# resistors_set.net
KiCad netlist of a schematic drawn in Altium Designer
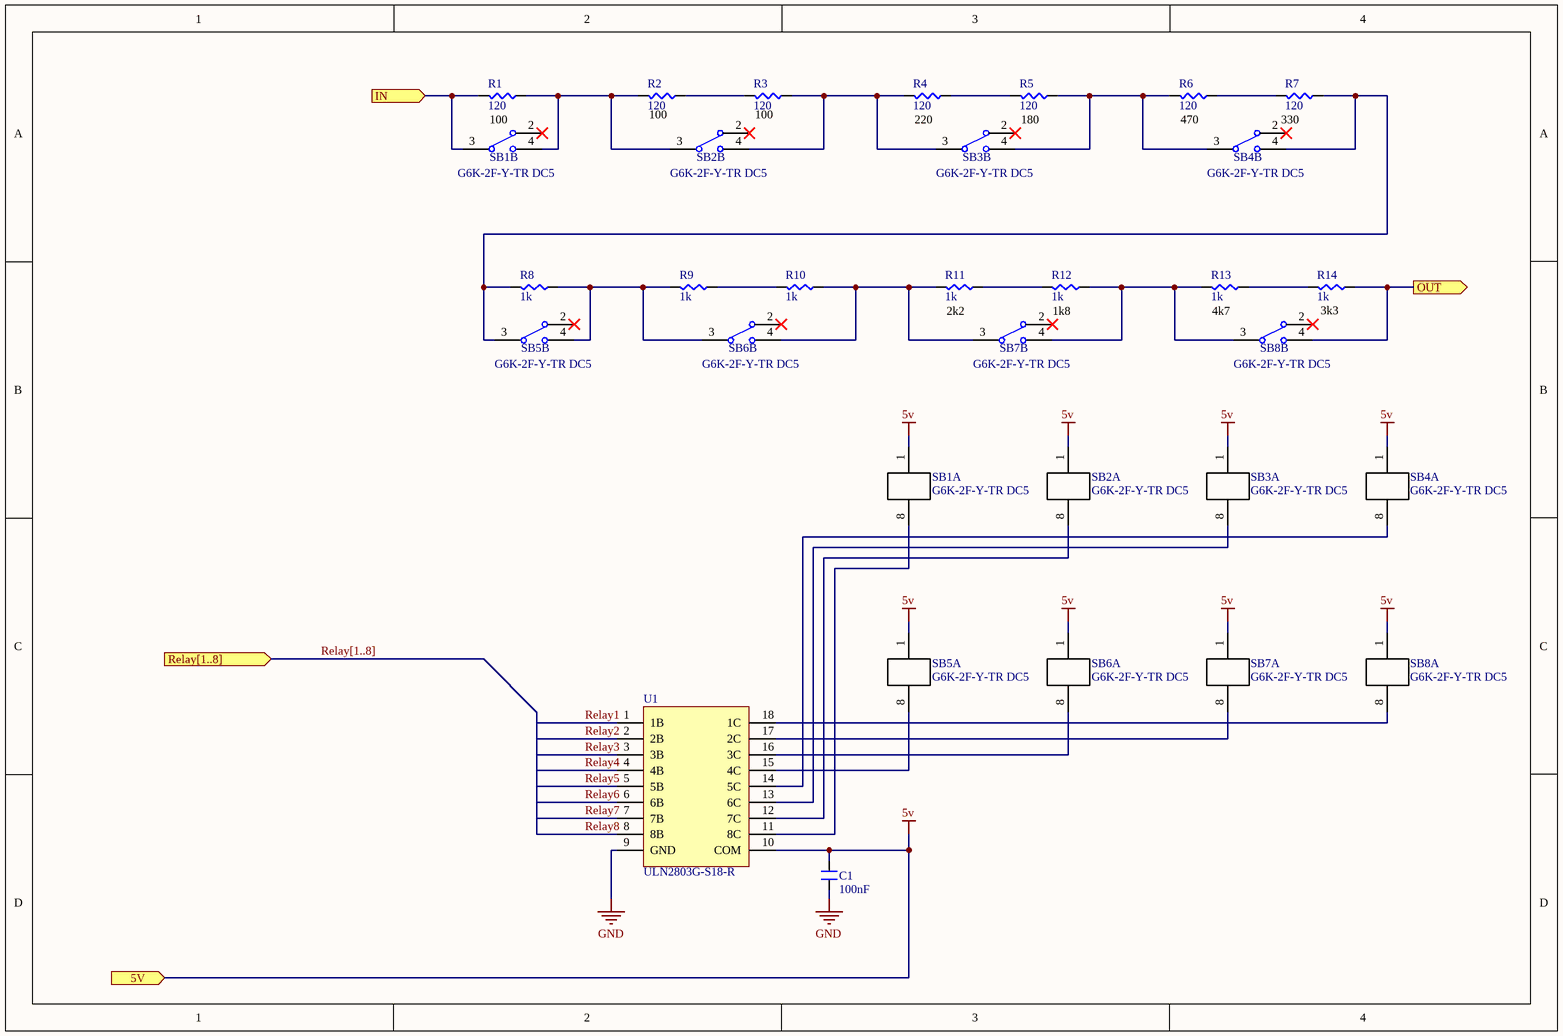
[diagram p0: resistors_set.SchDoc]

(export (version "E")
  (design (tool "Eeschema 10.0.6"))
  (components
    (comp (ref "C1")
      (value "100nF")
      (footprint "CAP0603")
      (description "Tolerance ±10%\nRated Voltage 50Vdc\nTemperature 0±30ppm/℃")
      (fields (field (name "PART NUMBER") "GCM188R71H104KA57J") (field (name "TOLERANCE") "10%"))
      (libsource (lib "Lib_Kam") (part "Capacitor"))
    )
    (comp (ref "R1")
      (value "120")
      (footprint "RES1206")
      (description "Tolerance ±1%\nPower (Watts) 0.25W, 1/4W\nTemperature Coefficient ±100ppm/°C")
      (fields (field (name "PART NUMBER") "CR1206-FX-1200ELF") (field (name "TOLERANCE") "1%"))
      (libsource (lib "Lib_Kam") (part "Resistor"))
    )
    (comp (ref "R2")
      (value "120")
      (footprint "RES1206")
      (description "Tolerance ±1%\nPower (Watts) 0.25W, 1/4W\nTemperature Coefficient ±100ppm/°C")
      (fields (field (name "PART NUMBER") "CR1206-FX-1200ELF") (field (name "TOLERANCE") "1%"))
      (libsource (lib "Lib_Kam") (part "Resistor"))
    )
    (comp (ref "R3")
      (value "120")
      (footprint "RES1206")
      (description "Tolerance ±1%\nPower (Watts) 0.25W, 1/4W\nTemperature Coefficient ±100ppm/°C")
      (fields (field (name "PART NUMBER") "CR1206-FX-1200ELF") (field (name "TOLERANCE") "1%"))
      (libsource (lib "Lib_Kam") (part "Resistor"))
    )
    (comp (ref "R4")
      (value "120")
      (footprint "RES1206")
      (description "Tolerance ±1%\nPower (Watts) 0.25W, 1/4W\nTemperature Coefficient ±100ppm/°C")
      (fields (field (name "PART NUMBER") "CR1206-FX-1200ELF") (field (name "TOLERANCE") "1%"))
      (libsource (lib "Lib_Kam") (part "Resistor"))
    )
    (comp (ref "R5")
      (value "120")
      (footprint "RES1206")
      (description "Tolerance ±1%\nPower (Watts) 0.25W, 1/4W\nTemperature Coefficient ±100ppm/°C")
      (fields (field (name "PART NUMBER") "CR1206-FX-1200ELF") (field (name "TOLERANCE") "1%"))
      (libsource (lib "Lib_Kam") (part "Resistor"))
    )
    (comp (ref "R6")
      (value "120")
      (footprint "RES1206")
      (description "Tolerance ±1%\nPower (Watts) 0.25W, 1/4W\nTemperature Coefficient ±100ppm/°C")
      (fields (field (name "PART NUMBER") "CR1206-FX-1200ELF") (field (name "TOLERANCE") "1%"))
      (libsource (lib "Lib_Kam") (part "Resistor"))
    )
    (comp (ref "R7")
      (value "120")
      (footprint "RES1206")
      (description "Tolerance ±1%\nPower (Watts) 0.25W, 1/4W\nTemperature Coefficient ±100ppm/°C")
      (fields (field (name "PART NUMBER") "CR1206-FX-1200ELF") (field (name "TOLERANCE") "1%"))
      (libsource (lib "Lib_Kam") (part "Resistor"))
    )
    (comp (ref "R8")
      (value "1k")
      (footprint "RES1206")
      (description "Tolerance ±1%\nPower (Watts) 0.1W, 1/10W\nTemperature Coefficient ±50ppm/°C")
      (fields (field (name "PART NUMBER") "CRT1206-FZ-1001ELF") (field (name "TOLERANCE") "1%"))
      (libsource (lib "Lib_Kam") (part "Resistor"))
    )
    (comp (ref "R9")
      (value "1k")
      (footprint "RES1206")
      (description "Tolerance ±1%\nPower (Watts) 0.1W, 1/10W\nTemperature Coefficient ±50ppm/°C")
      (fields (field (name "PART NUMBER") "CRT1206-FZ-1001ELF") (field (name "TOLERANCE") "1%"))
      (libsource (lib "Lib_Kam") (part "Resistor"))
    )
    (comp (ref "R10")
      (value "1k")
      (footprint "RES1206")
      (description "Tolerance ±1%\nPower (Watts) 0.1W, 1/10W\nTemperature Coefficient ±50ppm/°C")
      (fields (field (name "PART NUMBER") "CRT1206-FZ-1001ELF") (field (name "TOLERANCE") "1%"))
      (libsource (lib "Lib_Kam") (part "Resistor"))
    )
    (comp (ref "R11")
      (value "1k")
      (footprint "RES1206")
      (description "Tolerance ±1%\nPower (Watts) 0.1W, 1/10W\nTemperature Coefficient ±50ppm/°C")
      (fields (field (name "PART NUMBER") "CRT1206-FZ-1001ELF") (field (name "TOLERANCE") "1%"))
      (libsource (lib "Lib_Kam") (part "Resistor"))
    )
    (comp (ref "R12")
      (value "1k")
      (footprint "RES1206")
      (description "Tolerance ±1%\nPower (Watts) 0.1W, 1/10W\nTemperature Coefficient ±50ppm/°C")
      (fields (field (name "PART NUMBER") "CRT1206-FZ-1001ELF") (field (name "TOLERANCE") "1%"))
      (libsource (lib "Lib_Kam") (part "Resistor"))
    )
    (comp (ref "R13")
      (value "1k")
      (footprint "RES1206")
      (description "Tolerance ±1%\nPower (Watts) 0.1W, 1/10W\nTemperature Coefficient ±50ppm/°C")
      (fields (field (name "PART NUMBER") "CRT1206-FZ-1001ELF") (field (name "TOLERANCE") "1%"))
      (libsource (lib "Lib_Kam") (part "Resistor"))
    )
    (comp (ref "R14")
      (value "1k")
      (footprint "RES1206")
      (description "Tolerance ±1%\nPower (Watts) 0.1W, 1/10W\nTemperature Coefficient ±50ppm/°C")
      (fields (field (name "PART NUMBER") "CRT1206-FZ-1001ELF") (field (name "TOLERANCE") "1%"))
      (libsource (lib "Lib_Kam") (part "Resistor"))
    )
    (comp (ref "SB1")
      (value "G6K-2F-Y-TR DC5")
      (footprint "Omron_G6K-2F-Y")
      (description "1A 5V DPDT (2 Form C) SMD,6.5x10mm Signal Relays ROHS")
      (fields (field (name "MANUFACTURER") "Omron Electronics"))
      (libsource (lib "Lib_Kam") (part "Omron_G6K"))
    )
    (comp (ref "SB2")
      (value "G6K-2F-Y-TR DC5")
      (footprint "Omron_G6K-2F-Y")
      (description "1A 5V DPDT (2 Form C) SMD,6.5x10mm Signal Relays ROHS")
      (fields (field (name "MANUFACTURER") "Omron Electronics"))
      (libsource (lib "Lib_Kam") (part "Omron_G6K"))
    )
    (comp (ref "SB3")
      (value "G6K-2F-Y-TR DC5")
      (footprint "Omron_G6K-2F-Y")
      (description "1A 5V DPDT (2 Form C) SMD,6.5x10mm Signal Relays ROHS")
      (fields (field (name "MANUFACTURER") "Omron Electronics"))
      (libsource (lib "Lib_Kam") (part "Omron_G6K"))
    )
    (comp (ref "SB4")
      (value "G6K-2F-Y-TR DC5")
      (footprint "Omron_G6K-2F-Y")
      (description "1A 5V DPDT (2 Form C) SMD,6.5x10mm Signal Relays ROHS")
      (fields (field (name "MANUFACTURER") "Omron Electronics"))
      (libsource (lib "Lib_Kam") (part "Omron_G6K"))
    )
    (comp (ref "SB5")
      (value "G6K-2F-Y-TR DC5")
      (footprint "Omron_G6K-2F-Y")
      (description "1A 5V DPDT (2 Form C) SMD,6.5x10mm Signal Relays ROHS")
      (fields (field (name "MANUFACTURER") "Omron Electronics"))
      (libsource (lib "Lib_Kam") (part "Omron_G6K"))
    )
    (comp (ref "SB6")
      (value "G6K-2F-Y-TR DC5")
      (footprint "Omron_G6K-2F-Y")
      (description "1A 5V DPDT (2 Form C) SMD,6.5x10mm Signal Relays ROHS")
      (fields (field (name "MANUFACTURER") "Omron Electronics"))
      (libsource (lib "Lib_Kam") (part "Omron_G6K"))
    )
    (comp (ref "SB7")
      (value "G6K-2F-Y-TR DC5")
      (footprint "Omron_G6K-2F-Y")
      (description "1A 5V DPDT (2 Form C) SMD,6.5x10mm Signal Relays ROHS")
      (fields (field (name "MANUFACTURER") "Omron Electronics"))
      (libsource (lib "Lib_Kam") (part "Omron_G6K"))
    )
    (comp (ref "SB8")
      (value "G6K-2F-Y-TR DC5")
      (footprint "Omron_G6K-2F-Y")
      (description "1A 5V DPDT (2 Form C) SMD,6.5x10mm Signal Relays ROHS")
      (fields (field (name "MANUFACTURER") "Omron Electronics"))
      (libsource (lib "Lib_Kam") (part "Omron_G6K"))
    )
    (comp (ref "U1")
      (value "ULN2803G-S18-R")
      (footprint "SOIC-18-wide")
      (description "SOP-18 Darlington Transistor Arrays ROHS")
      (fields (field (name "MANUFACTURER") "UTC(Unisonic Tech)"))
      (libsource (lib "Lib_Kam") (part "ULN2803"))
    )
  )
  (nets
    (net (code "1") (name "/IN") (class "Default")
      (node (ref "R1") (pin "1") (pintype "passive"))
      (node (ref "SB1") (pin "3") (pintype "passive"))
    )
    (net (code "2") (name "/OUT") (class "Default")
      (node (ref "R14") (pin "2") (pintype "passive"))
      (node (ref "SB8") (pin "4") (pintype "passive"))
    )
    (net (code "3") (name "/Relay1") (class "Default")
      (node (ref "U1") (pin "1") (pinfunction "1B_1") (pintype "passive"))
    )
    (net (code "4") (name "/Relay2") (class "Default")
      (node (ref "U1") (pin "2") (pinfunction "2B_2") (pintype "passive"))
    )
    (net (code "5") (name "/Relay3") (class "Default")
      (node (ref "U1") (pin "3") (pinfunction "3B_3") (pintype "passive"))
    )
    (net (code "6") (name "/Relay4") (class "Default")
      (node (ref "U1") (pin "4") (pinfunction "4B_4") (pintype "passive"))
    )
    (net (code "7") (name "/Relay5") (class "Default")
      (node (ref "U1") (pin "5") (pinfunction "5B_5") (pintype "passive"))
    )
    (net (code "8") (name "/Relay6") (class "Default")
      (node (ref "U1") (pin "6") (pinfunction "6B_6") (pintype "passive"))
    )
    (net (code "9") (name "/Relay7") (class "Default")
      (node (ref "U1") (pin "7") (pinfunction "7B_7") (pintype "passive"))
    )
    (net (code "10") (name "/Relay8") (class "Default")
      (node (ref "U1") (pin "8") (pinfunction "8B_8") (pintype "passive"))
    )
    (net (code "12") (name "5v") (class "Default")
      (node (ref "C1") (pin "2") (pinfunction "2_2") (pintype "passive"))
      (node (ref "SB1") (pin "1") (pintype "passive"))
      (node (ref "SB2") (pin "1") (pintype "passive"))
      (node (ref "SB3") (pin "1") (pintype "passive"))
      (node (ref "SB4") (pin "1") (pintype "passive"))
      (node (ref "SB5") (pin "1") (pintype "passive"))
      (node (ref "SB6") (pin "1") (pintype "passive"))
      (node (ref "SB7") (pin "1") (pintype "passive"))
      (node (ref "SB8") (pin "1") (pintype "passive"))
      (node (ref "U1") (pin "10") (pinfunction "COM_10") (pintype "passive"))
    )
    (net (code "13") (name "GND") (class "Default")
      (node (ref "C1") (pin "1") (pinfunction "2_1") (pintype "passive"))
      (node (ref "U1") (pin "9") (pinfunction "GND_9") (pintype "passive"))
    )
    (net (code "14") (name "Net-(R1-Pad2)") (class "Default")
      (node (ref "R1") (pin "2") (pintype "passive"))
      (node (ref "R2") (pin "1") (pintype "passive"))
      (node (ref "SB1") (pin "4") (pintype "passive"))
      (node (ref "SB2") (pin "3") (pintype "passive"))
    )
    (net (code "15") (name "Net-(R2-Pad2)") (class "Default")
      (node (ref "R2") (pin "2") (pintype "passive"))
      (node (ref "R3") (pin "1") (pintype "passive"))
    )
    (net (code "16") (name "Net-(R3-Pad2)") (class "Default")
      (node (ref "R3") (pin "2") (pintype "passive"))
      (node (ref "R4") (pin "1") (pintype "passive"))
      (node (ref "SB2") (pin "4") (pintype "passive"))
      (node (ref "SB3") (pin "3") (pintype "passive"))
    )
    (net (code "17") (name "Net-(R4-Pad2)") (class "Default")
      (node (ref "R4") (pin "2") (pintype "passive"))
      (node (ref "R5") (pin "1") (pintype "passive"))
    )
    (net (code "18") (name "Net-(R5-Pad2)") (class "Default")
      (node (ref "R5") (pin "2") (pintype "passive"))
      (node (ref "R6") (pin "1") (pintype "passive"))
      (node (ref "SB3") (pin "4") (pintype "passive"))
      (node (ref "SB4") (pin "3") (pintype "passive"))
    )
    (net (code "19") (name "Net-(R6-Pad2)") (class "Default")
      (node (ref "R6") (pin "2") (pintype "passive"))
      (node (ref "R7") (pin "1") (pintype "passive"))
    )
    (net (code "20") (name "Net-(R7-Pad2)") (class "Default")
      (node (ref "R7") (pin "2") (pintype "passive"))
      (node (ref "R8") (pin "1") (pintype "passive"))
      (node (ref "SB4") (pin "4") (pintype "passive"))
      (node (ref "SB5") (pin "3") (pintype "passive"))
    )
    (net (code "21") (name "Net-(R8-Pad2)") (class "Default")
      (node (ref "R8") (pin "2") (pintype "passive"))
      (node (ref "R9") (pin "1") (pintype "passive"))
      (node (ref "SB5") (pin "4") (pintype "passive"))
      (node (ref "SB6") (pin "3") (pintype "passive"))
    )
    (net (code "22") (name "Net-(R10-Pad1)") (class "Default")
      (node (ref "R10") (pin "1") (pintype "passive"))
      (node (ref "R9") (pin "2") (pintype "passive"))
    )
    (net (code "23") (name "Net-(R10-Pad2)") (class "Default")
      (node (ref "R10") (pin "2") (pintype "passive"))
      (node (ref "R11") (pin "1") (pintype "passive"))
      (node (ref "SB6") (pin "4") (pintype "passive"))
      (node (ref "SB7") (pin "3") (pintype "passive"))
    )
    (net (code "24") (name "Net-(R11-Pad2)") (class "Default")
      (node (ref "R11") (pin "2") (pintype "passive"))
      (node (ref "R12") (pin "1") (pintype "passive"))
    )
    (net (code "25") (name "Net-(R12-Pad2)") (class "Default")
      (node (ref "R12") (pin "2") (pintype "passive"))
      (node (ref "R13") (pin "1") (pintype "passive"))
      (node (ref "SB7") (pin "4") (pintype "passive"))
      (node (ref "SB8") (pin "3") (pintype "passive"))
    )
    (net (code "26") (name "Net-(R13-Pad2)") (class "Default")
      (node (ref "R13") (pin "2") (pintype "passive"))
      (node (ref "R14") (pin "1") (pintype "passive"))
    )
    (net (code "27") (name "Net-(U1-1C)") (class "Default")
      (node (ref "SB8") (pin "8") (pintype "passive"))
      (node (ref "U1") (pin "18") (pinfunction "1C_18") (pintype "passive"))
    )
    (net (code "28") (name "Net-(U1-2C)") (class "Default")
      (node (ref "SB7") (pin "8") (pintype "passive"))
      (node (ref "U1") (pin "17") (pinfunction "2C_17") (pintype "passive"))
    )
    (net (code "29") (name "Net-(U1-3C)") (class "Default")
      (node (ref "SB6") (pin "8") (pintype "passive"))
      (node (ref "U1") (pin "16") (pinfunction "3C_16") (pintype "passive"))
    )
    (net (code "30") (name "Net-(U1-4C)") (class "Default")
      (node (ref "SB5") (pin "8") (pintype "passive"))
      (node (ref "U1") (pin "15") (pinfunction "4C_15") (pintype "passive"))
    )
    (net (code "31") (name "Net-(U1-5C)") (class "Default")
      (node (ref "SB4") (pin "8") (pintype "passive"))
      (node (ref "U1") (pin "14") (pinfunction "5C_14") (pintype "passive"))
    )
    (net (code "32") (name "Net-(U1-6C)") (class "Default")
      (node (ref "SB3") (pin "8") (pintype "passive"))
      (node (ref "U1") (pin "13") (pinfunction "6C_13") (pintype "passive"))
    )
    (net (code "33") (name "Net-(U1-7C)") (class "Default")
      (node (ref "SB2") (pin "8") (pintype "passive"))
      (node (ref "U1") (pin "12") (pinfunction "7C_12") (pintype "passive"))
    )
    (net (code "34") (name "Net-(U1-8C)") (class "Default")
      (node (ref "SB1") (pin "8") (pintype "passive"))
      (node (ref "U1") (pin "11") (pinfunction "8C_11") (pintype "passive"))
    )
    (net (code "35") (name "unconnected-(SB1-Pad2)") (class "Default")
      (node (ref "SB1") (pin "2") (pintype "passive+no_connect"))
    )
    (net (code "36") (name "unconnected-(SB2-Pad2)") (class "Default")
      (node (ref "SB2") (pin "2") (pintype "passive+no_connect"))
    )
    (net (code "37") (name "unconnected-(SB3-Pad2)") (class "Default")
      (node (ref "SB3") (pin "2") (pintype "passive+no_connect"))
    )
    (net (code "38") (name "unconnected-(SB4-Pad2)") (class "Default")
      (node (ref "SB4") (pin "2") (pintype "passive+no_connect"))
    )
    (net (code "39") (name "unconnected-(SB5-Pad2)") (class "Default")
      (node (ref "SB5") (pin "2") (pintype "passive+no_connect"))
    )
    (net (code "40") (name "unconnected-(SB6-Pad2)") (class "Default")
      (node (ref "SB6") (pin "2") (pintype "passive+no_connect"))
    )
    (net (code "41") (name "unconnected-(SB7-Pad2)") (class "Default")
      (node (ref "SB7") (pin "2") (pintype "passive+no_connect"))
    )
    (net (code "42") (name "unconnected-(SB8-Pad2)") (class "Default")
      (node (ref "SB8") (pin "2") (pintype "passive+no_connect"))
    )
  )
)
